# Model3_v1_0.net
KiCad netlist of a schematic drawn in Altium Designer
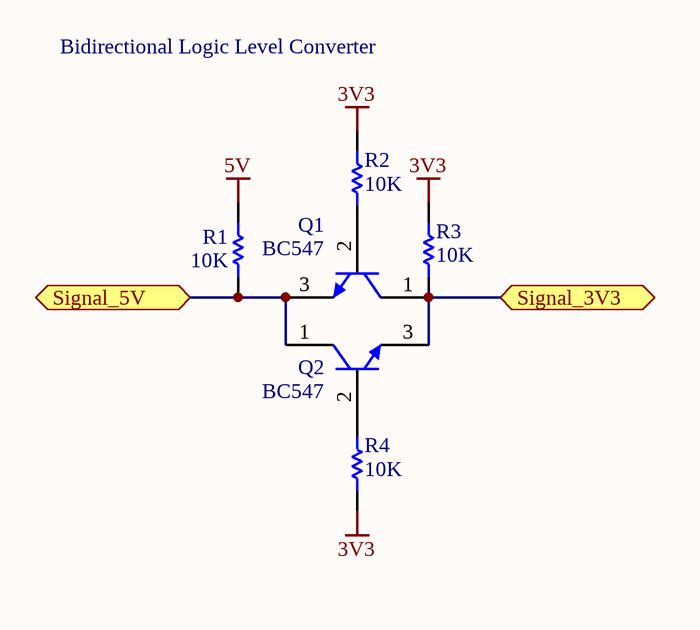
[diagram p0: Model3_v1.0.SchDoc]

(export (version "E")
  (design (tool "Eeschema 10.0.6"))
  (components
    (comp (ref "Q1")
      (value "BC547")
      (footprint "TO92_3Pin")
      (description "Transistor, BJT, NPN")
      (libsource (lib "General") (part "Transistor_BJT_NPN_cbe"))
    )
    (comp (ref "Q2")
      (value "BC547")
      (footprint "TO92_3Pin")
      (description "Transistor, BJT, NPN")
      (libsource (lib "General") (part "Transistor_BJT_NPN_cbe"))
    )
    (comp (ref "R1")
      (value "10K")
      (footprint "SMD_0805")
      (description "Resistor, 1/4W, 5%")
      (libsource (lib "General") (part "Resistor"))
    )
    (comp (ref "R2")
      (value "10K")
      (footprint "SMD_0805")
      (description "Resistor, 1/4W, 5%")
      (libsource (lib "General") (part "Resistor"))
    )
    (comp (ref "R3")
      (value "10K")
      (footprint "SMD_0805")
      (description "Resistor, 1/4W, 5%")
      (libsource (lib "General") (part "Resistor"))
    )
    (comp (ref "R4")
      (value "10K")
      (footprint "SMD_0805")
      (description "Resistor, 1/4W, 5%")
      (libsource (lib "General") (part "Resistor"))
    )
  )
  (nets
    (net (code "1") (name "/Signal_3V3") (class "Default")
      (node (ref "Q1") (pin "1") (pinfunction "C_1") (pintype "passive"))
      (node (ref "Q2") (pin "3") (pinfunction "E_3") (pintype "passive"))
      (node (ref "R3") (pin "1") (pinfunction "1_1") (pintype "passive"))
    )
    (net (code "2") (name "/Signal_5V") (class "Default")
      (node (ref "Q1") (pin "3") (pinfunction "E_3") (pintype "passive"))
      (node (ref "Q2") (pin "1") (pinfunction "C_1") (pintype "passive"))
      (node (ref "R1") (pin "1") (pinfunction "1_1") (pintype "passive"))
    )
    (net (code "3") (name "3V3") (class "Default")
      (node (ref "R2") (pin "2") (pinfunction "2_2") (pintype "passive"))
      (node (ref "R3") (pin "2") (pinfunction "2_2") (pintype "passive"))
      (node (ref "R4") (pin "1") (pinfunction "1_1") (pintype "passive"))
    )
    (net (code "4") (name "5V") (class "Default")
      (node (ref "R1") (pin "2") (pinfunction "2_2") (pintype "passive"))
    )
    (net (code "5") (name "Net-(Q1-B)") (class "Default")
      (node (ref "Q1") (pin "2") (pinfunction "B_2") (pintype "passive"))
      (node (ref "R2") (pin "1") (pinfunction "1_1") (pintype "passive"))
    )
    (net (code "6") (name "Net-(Q2-B)") (class "Default")
      (node (ref "Q2") (pin "2") (pinfunction "B_2") (pintype "passive"))
      (node (ref "R4") (pin "2") (pinfunction "2_2") (pintype "passive"))
    )
  )
)
